# BV10011_ControlUSBSerial.net
KiCad netlist of a schematic drawn in Altium Designer
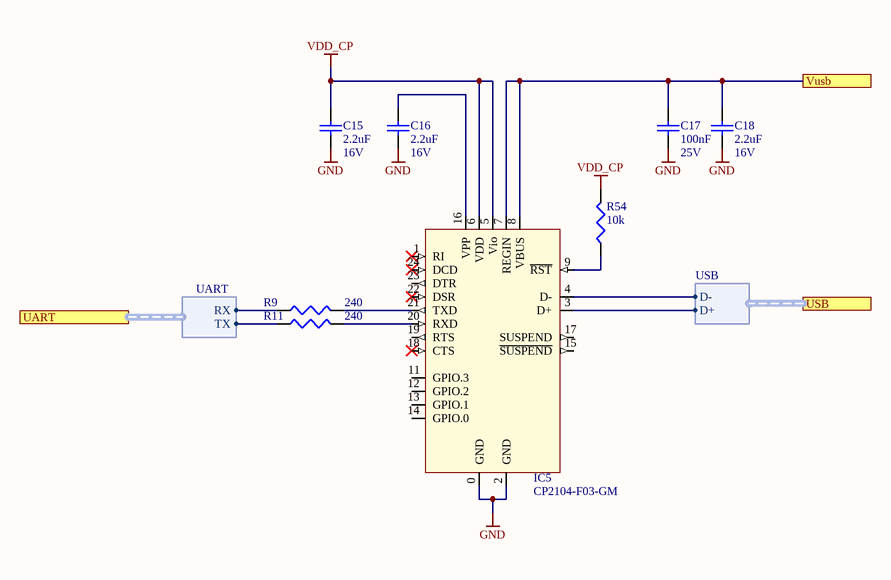
[diagram p0: BV10011_ControlUSBSerial.SchDoc]

(export (version "E")
  (design (tool "Eeschema 10.0.6"))
  (components
    (comp (ref "C15")
      (value "2.2uF")
      (footprint "C0603")
      (description "Capacitor, 2.2uF, 16V, X5R")
      (fields (field (name "VOLTAGE RATING") "16V"))
      (libsource (lib "AR_Capacitors_Ceramic") (part "2.2uF/0603/CER/16V"))
    )
    (comp (ref "C16")
      (value "2.2uF")
      (footprint "C0603")
      (description "Capacitor, 2.2uF, 16V, X5R")
      (fields (field (name "VOLTAGE RATING") "16V"))
      (libsource (lib "AR_Capacitors_Ceramic") (part "2.2uF/0603/CER/16V"))
    )
    (comp (ref "C17")
      (value "100nF")
      (footprint "C0402")
      (description "Capacitor, 100nF, 25V, X7R")
      (fields (field (name "VOLTAGE RATING") "25V"))
      (libsource (lib "AR_Capacitors_Ceramic") (part "100nF/0402/CER/25V"))
    )
    (comp (ref "C18")
      (value "2.2uF")
      (footprint "C0603")
      (description "Capacitor, 2.2uF, 16V, X5R")
      (fields (field (name "VOLTAGE RATING") "16V"))
      (libsource (lib "AR_Capacitors_Ceramic") (part "2.2uF/0603/CER/16V"))
    )
    (comp (ref "IC5")
      (value "CP2104-F03-GM")
      (footprint "QFN24")
      (description "USB to UART converter")
      (libsource (lib "AR_ICs") (part "CP2104-F03-GM"))
    )
    (comp (ref "R9")
      (value "240")
      (footprint "0402")
      (description "Resistor, 240, 0.1%, 0.0625W, 50V, 100PPM, 0402")
      (libsource (lib "AR_Resistors_SMD") (part "240/0402/0063W/50V"))
    )
    (comp (ref "R11")
      (value "240")
      (footprint "0402")
      (description "Resistor, 240, 0.1%, 0.0625W, 50V, 100PPM, 0402")
      (libsource (lib "AR_Resistors_SMD") (part "240/0402/0063W/50V"))
    )
    (comp (ref "R54")
      (value "10k")
      (footprint "0402")
      (description "Resistor, 10k, 0.1%, 0.0625W, 50V, 100PPM, 0402")
      (libsource (lib "AR_Resistors_SMD") (part "10k/0402/0063W/50V"))
    )
  )
  (nets
    (net (code "3") (name "/D+") (class "Default")
      (node (ref "IC5") (pin "3") (pinfunction "D+_3") (pintype "bidirectional"))
    )
    (net (code "4") (name "/D-") (class "Default")
      (node (ref "IC5") (pin "4") (pinfunction "D-_4") (pintype "bidirectional"))
    )
    (net (code "5") (name "/RX") (class "Default")
      (node (ref "R9") (pin "1") (pinfunction "1_1") (pintype "passive"))
    )
    (net (code "6") (name "/TX") (class "Default")
      (node (ref "R11") (pin "1") (pinfunction "1_1") (pintype "passive"))
    )
    (net (code "7") (name "/Vusb") (class "Default")
      (node (ref "C17") (pin "2") (pinfunction "2_2") (pintype "passive"))
      (node (ref "C18") (pin "2") (pinfunction "2_2") (pintype "passive"))
      (node (ref "IC5") (pin "7") (pinfunction "REGIN_7") (pintype "power_in"))
      (node (ref "IC5") (pin "8") (pinfunction "VBUS_8") (pintype "power_in"))
    )
    (net (code "10") (name "GND") (class "Default")
      (node (ref "C15") (pin "1") (pinfunction "1_1") (pintype "passive"))
      (node (ref "C16") (pin "1") (pinfunction "1_1") (pintype "passive"))
      (node (ref "C17") (pin "1") (pinfunction "1_1") (pintype "passive"))
      (node (ref "C18") (pin "1") (pinfunction "1_1") (pintype "passive"))
      (node (ref "IC5") (pin "0") (pinfunction "GND_0") (pintype "power_in"))
      (node (ref "IC5") (pin "2") (pinfunction "GND_2") (pintype "power_in"))
    )
    (net (code "11") (name "Net-(IC5-RXD)") (class "Default")
      (node (ref "IC5") (pin "20") (pinfunction "RXD_20") (pintype "input"))
      (node (ref "R11") (pin "2") (pinfunction "2_2") (pintype "passive"))
    )
    (net (code "12") (name "Net-(IC5-TXD)") (class "Default")
      (node (ref "IC5") (pin "21") (pinfunction "TXD_21") (pintype "output"))
      (node (ref "R9") (pin "2") (pinfunction "2_2") (pintype "passive"))
    )
    (net (code "13") (name "Net-(IC5-VPP)") (class "Default")
      (node (ref "C16") (pin "2") (pinfunction "2_2") (pintype "passive"))
      (node (ref "IC5") (pin "16") (pinfunction "VPP_16") (pintype "power_in"))
    )
    (net (code "14") (name "Net-(IC5-~{RST})") (class "Default")
      (node (ref "IC5") (pin "9") (pinfunction "~{RST}_9") (pintype "input"))
      (node (ref "R54") (pin "1") (pinfunction "1_1") (pintype "passive"))
    )
    (net (code "15") (name "VDD_CP") (class "Default")
      (node (ref "C15") (pin "2") (pinfunction "2_2") (pintype "passive"))
      (node (ref "IC5") (pin "5") (pinfunction "Vio_5") (pintype "passive"))
      (node (ref "IC5") (pin "6") (pinfunction "VDD_6") (pintype "power_in"))
      (node (ref "R54") (pin "2") (pinfunction "2_2") (pintype "passive"))
    )
    (net (code "16") (name "unconnected-(IC5-CTS-Pad18)") (class "Default")
      (node (ref "IC5") (pin "18") (pinfunction "CTS_18") (pintype "input+no_connect"))
    )
    (net (code "17") (name "unconnected-(IC5-DCD-Pad24)") (class "Default")
      (node (ref "IC5") (pin "24") (pinfunction "DCD_24") (pintype "input+no_connect"))
    )
    (net (code "18") (name "unconnected-(IC5-DSR-Pad22)") (class "Default")
      (node (ref "IC5") (pin "22") (pinfunction "DSR_22") (pintype "input+no_connect"))
    )
    (net (code "19") (name "unconnected-(IC5-DTR-Pad23)") (class "Default")
      (node (ref "IC5") (pin "23") (pinfunction "DTR_23") (pintype "output"))
    )
    (net (code "20") (name "unconnected-(IC5-GPIO.0-Pad14)") (class "Default")
      (node (ref "IC5") (pin "14") (pinfunction "GPIO.0_14") (pintype "passive"))
    )
    (net (code "21") (name "unconnected-(IC5-GPIO.1-Pad13)") (class "Default")
      (node (ref "IC5") (pin "13") (pinfunction "GPIO.1_13") (pintype "passive"))
    )
    (net (code "22") (name "unconnected-(IC5-GPIO.2-Pad12)") (class "Default")
      (node (ref "IC5") (pin "12") (pinfunction "GPIO.2_12") (pintype "passive"))
    )
    (net (code "23") (name "unconnected-(IC5-GPIO.3-Pad11)") (class "Default")
      (node (ref "IC5") (pin "11") (pinfunction "GPIO.3_11") (pintype "passive"))
    )
    (net (code "24") (name "unconnected-(IC5-RI-Pad1)") (class "Default")
      (node (ref "IC5") (pin "1") (pinfunction "RI_1") (pintype "input+no_connect"))
    )
    (net (code "25") (name "unconnected-(IC5-RTS-Pad19)") (class "Default")
      (node (ref "IC5") (pin "19") (pinfunction "RTS_19") (pintype "output"))
    )
    (net (code "26") (name "unconnected-(IC5-SUSPEND-Pad17)") (class "Default")
      (node (ref "IC5") (pin "17") (pinfunction "SUSPEND_17") (pintype "output"))
    )
    (net (code "27") (name "unconnected-(IC5-~{SUSPEND}-Pad15)") (class "Default")
      (node (ref "IC5") (pin "15") (pinfunction "~{SUSPEND}_15") (pintype "output"))
    )
  )
)
